# Hx711_schematic_V1.net
KiCad netlist of a schematic drawn in EAGLE
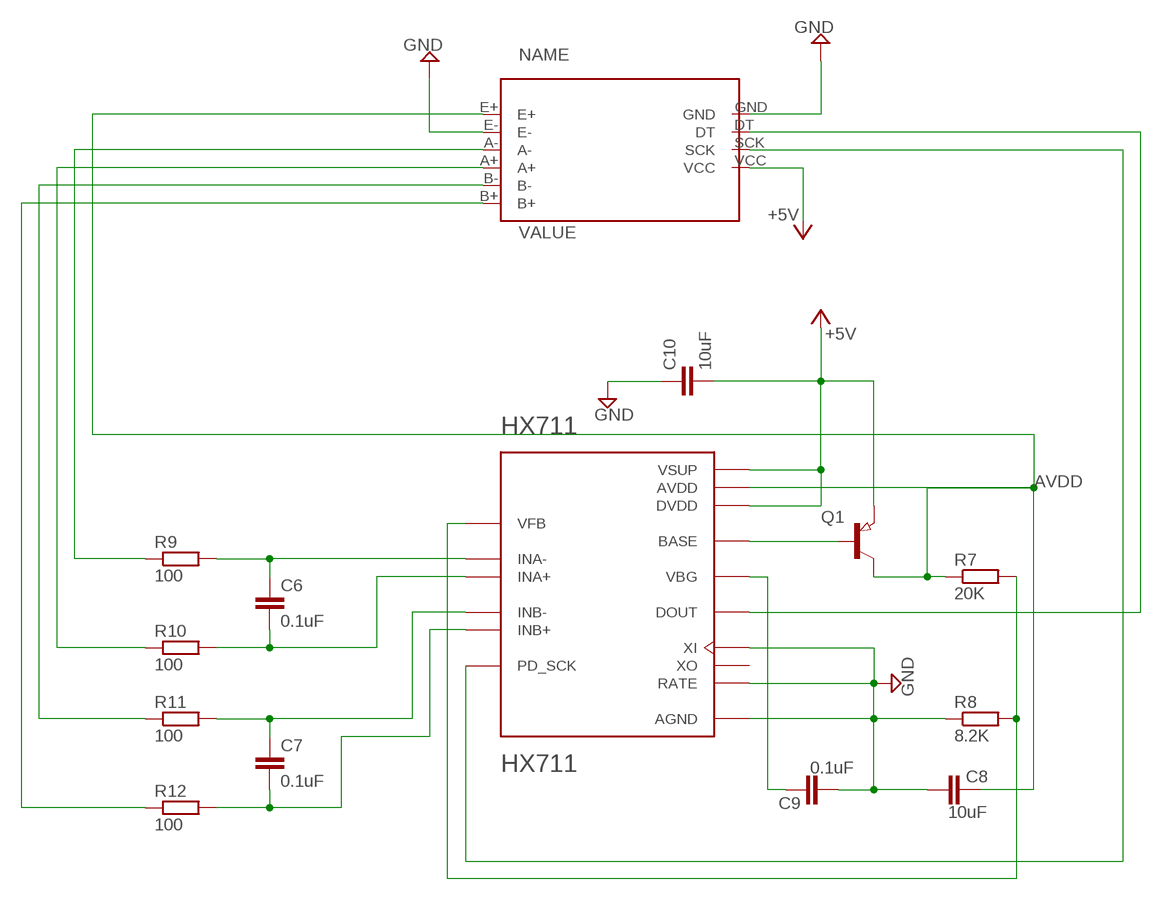
[diagram p0: schematic, sheet 1]

(export (version "E")
  (design (tool "Eeschema 10.0.6"))
  (components
    (comp (ref "C6")
      (value "0.1uF")
      (footprint "eagle-import:C2.5-2")
      (libsource (lib "eagle-import") (part "C2.5/2"))
    )
    (comp (ref "C7")
      (value "0.1uF")
      (footprint "eagle-import:C2.5-2")
      (libsource (lib "eagle-import") (part "C2.5/2"))
    )
    (comp (ref "C8")
      (value "10uF")
      (footprint "eagle-import:C2.5-2")
      (libsource (lib "eagle-import") (part "C2.5/2"))
    )
    (comp (ref "C9")
      (value "0.1uF")
      (footprint "eagle-import:C2.5-2")
      (libsource (lib "eagle-import") (part "C2.5/2"))
    )
    (comp (ref "C10")
      (value "10uF")
      (footprint "eagle-import:C2.5-2")
      (libsource (lib "eagle-import") (part "C2.5/2"))
    )
    (comp (ref "HX711")
      (value "HX711")
      (footprint "eagle-import:SOP127P600X180-16N")
      (fields (field (name "MF") "AVIA SEMICONDUCTOR"))
      (libsource (lib "eagle-import") (part "HX711"))
    )
    (comp (ref "Q1")
      (value "PNP-TRANSISTOR_SOT23")
      (footprint "eagle-import:SOT23")
      (libsource (lib "eagle-import") (part "PNP-TRANSISTOR_SOT23"))
    )
    (comp (ref "R7")
      (value "20K")
      (footprint "eagle-import:R0603")
      (libsource (lib "eagle-import") (part "R-EU_R0603"))
    )
    (comp (ref "R8")
      (value "8.2K")
      (footprint "eagle-import:R0603")
      (libsource (lib "eagle-import") (part "R-EU_R0603"))
    )
    (comp (ref "R9")
      (value "100")
      (footprint "eagle-import:R0603")
      (libsource (lib "eagle-import") (part "R-EU_R0603"))
    )
    (comp (ref "R10")
      (value "100")
      (footprint "eagle-import:R0603")
      (libsource (lib "eagle-import") (part "R-EU_R0603"))
    )
    (comp (ref "R11")
      (value "100")
      (footprint "eagle-import:R0603")
      (libsource (lib "eagle-import") (part "R-EU_R0603"))
    )
    (comp (ref "R12")
      (value "100")
      (footprint "eagle-import:R0603")
      (libsource (lib "eagle-import") (part "R-EU_R0603"))
    )
    (comp (ref "U$1")
      (value "HX711A")
      (footprint "eagle-import:HX711")
      (libsource (lib "eagle-import") (part "HX711A"))
    )
  )
  (nets
    (net (code "1") (name "+5V") (class "Default")
      (node (ref "C10") (pin "2") (pinfunction "2_2") (pintype "passive"))
      (node (ref "HX711") (pin "1") (pinfunction "VSUP_1") (pintype "power_in"))
      (node (ref "HX711") (pin "16") (pinfunction "DVDD_16") (pintype "power_in"))
      (node (ref "Q1") (pin "2") (pinfunction "E_2") (pintype "passive"))
      (node (ref "U$1") (pin "VCC") (pinfunction "VCC_VCC") (pintype "bidirectional"))
    )
    (net (code "2") (name "/AVDD") (class "Default")
      (node (ref "C8") (pin "1") (pinfunction "1_1") (pintype "passive"))
      (node (ref "HX711") (pin "3") (pinfunction "AVDD_3") (pintype "power_in"))
      (node (ref "Q1") (pin "3") (pinfunction "C_3") (pintype "passive"))
      (node (ref "R7") (pin "1") (pinfunction "1_1") (pintype "passive"))
      (node (ref "U$1") (pin "E+") (pinfunction "E+_E+") (pintype "bidirectional"))
    )
    (net (code "3") (name "GND") (class "Default")
      (node (ref "C10") (pin "1") (pinfunction "1_1") (pintype "passive"))
      (node (ref "C8") (pin "2") (pinfunction "2_2") (pintype "passive"))
      (node (ref "C9") (pin "2") (pinfunction "2_2") (pintype "passive"))
      (node (ref "HX711") (pin "14") (pinfunction "XI_14") (pintype "input"))
      (node (ref "HX711") (pin "15") (pinfunction "RATE_15") (pintype "input"))
      (node (ref "HX711") (pin "5") (pinfunction "AGND_5") (pintype "power_in"))
      (node (ref "R8") (pin "1") (pinfunction "1_1") (pintype "passive"))
      (node (ref "U$1") (pin "E-") (pinfunction "E-_E-") (pintype "bidirectional"))
      (node (ref "U$1") (pin "GND") (pinfunction "GND_GND") (pintype "bidirectional"))
    )
    (net (code "4") (name "Net-(HX711-BASE)") (class "Default")
      (node (ref "HX711") (pin "2") (pinfunction "BASE_2") (pintype "output"))
      (node (ref "Q1") (pin "1") (pinfunction "B_1") (pintype "passive"))
    )
    (net (code "5") (name "Net-(HX711-DOUT)") (class "Default")
      (node (ref "HX711") (pin "12") (pinfunction "DOUT_12") (pintype "output"))
      (node (ref "U$1") (pin "DT") (pinfunction "DT_DT") (pintype "bidirectional"))
    )
    (net (code "6") (name "Net-(HX711-INA+)") (class "Default")
      (node (ref "C6") (pin "2") (pinfunction "2_2") (pintype "passive"))
      (node (ref "HX711") (pin "8") (pinfunction "INA+_8") (pintype "input"))
      (node (ref "R10") (pin "2") (pinfunction "2_2") (pintype "passive"))
    )
    (net (code "7") (name "Net-(HX711-INA-)") (class "Default")
      (node (ref "C6") (pin "1") (pinfunction "1_1") (pintype "passive"))
      (node (ref "HX711") (pin "7") (pinfunction "INA-_7") (pintype "input"))
      (node (ref "R9") (pin "2") (pinfunction "2_2") (pintype "passive"))
    )
    (net (code "8") (name "Net-(HX711-INB+)") (class "Default")
      (node (ref "C7") (pin "2") (pinfunction "2_2") (pintype "passive"))
      (node (ref "HX711") (pin "10") (pinfunction "INB+_10") (pintype "input"))
      (node (ref "R12") (pin "2") (pinfunction "2_2") (pintype "passive"))
    )
    (net (code "9") (name "Net-(HX711-INB-)") (class "Default")
      (node (ref "C7") (pin "1") (pinfunction "1_1") (pintype "passive"))
      (node (ref "HX711") (pin "9") (pinfunction "INB-_9") (pintype "input"))
      (node (ref "R11") (pin "2") (pinfunction "2_2") (pintype "passive"))
    )
    (net (code "10") (name "Net-(HX711-PD_SCK)") (class "Default")
      (node (ref "HX711") (pin "11") (pinfunction "PD_SCK_11") (pintype "input"))
      (node (ref "U$1") (pin "SCK") (pinfunction "SCK_SCK") (pintype "bidirectional"))
    )
    (net (code "11") (name "Net-(HX711-VBG)") (class "Default")
      (node (ref "C9") (pin "1") (pinfunction "1_1") (pintype "passive"))
      (node (ref "HX711") (pin "6") (pinfunction "VBG_6") (pintype "output"))
    )
    (net (code "12") (name "Net-(HX711-VFB)") (class "Default")
      (node (ref "HX711") (pin "4") (pinfunction "VFB_4") (pintype "input"))
      (node (ref "R7") (pin "2") (pinfunction "2_2") (pintype "passive"))
      (node (ref "R8") (pin "2") (pinfunction "2_2") (pintype "passive"))
    )
    (net (code "13") (name "Net-(R9-Pad1)") (class "Default")
      (node (ref "R9") (pin "1") (pinfunction "1_1") (pintype "passive"))
      (node (ref "U$1") (pin "A-") (pinfunction "A-_A-") (pintype "bidirectional"))
    )
    (net (code "14") (name "Net-(R10-Pad1)") (class "Default")
      (node (ref "R10") (pin "1") (pinfunction "1_1") (pintype "passive"))
      (node (ref "U$1") (pin "A+") (pinfunction "A+_A+") (pintype "bidirectional"))
    )
    (net (code "15") (name "Net-(R11-Pad1)") (class "Default")
      (node (ref "R11") (pin "1") (pinfunction "1_1") (pintype "passive"))
      (node (ref "U$1") (pin "B-") (pinfunction "B-_B-") (pintype "bidirectional"))
    )
    (net (code "16") (name "Net-(R12-Pad1)") (class "Default")
      (node (ref "R12") (pin "1") (pinfunction "1_1") (pintype "passive"))
      (node (ref "U$1") (pin "B+") (pinfunction "B+_B+") (pintype "bidirectional"))
    )
    (net (code "17") (name "unconnected-(HX711-XO-Pad13)") (class "Default")
      (node (ref "HX711") (pin "13") (pinfunction "XO_13") (pintype "output"))
    )
  )
)
